# MB.net
KiCad netlist of a schematic drawn in EAGLE
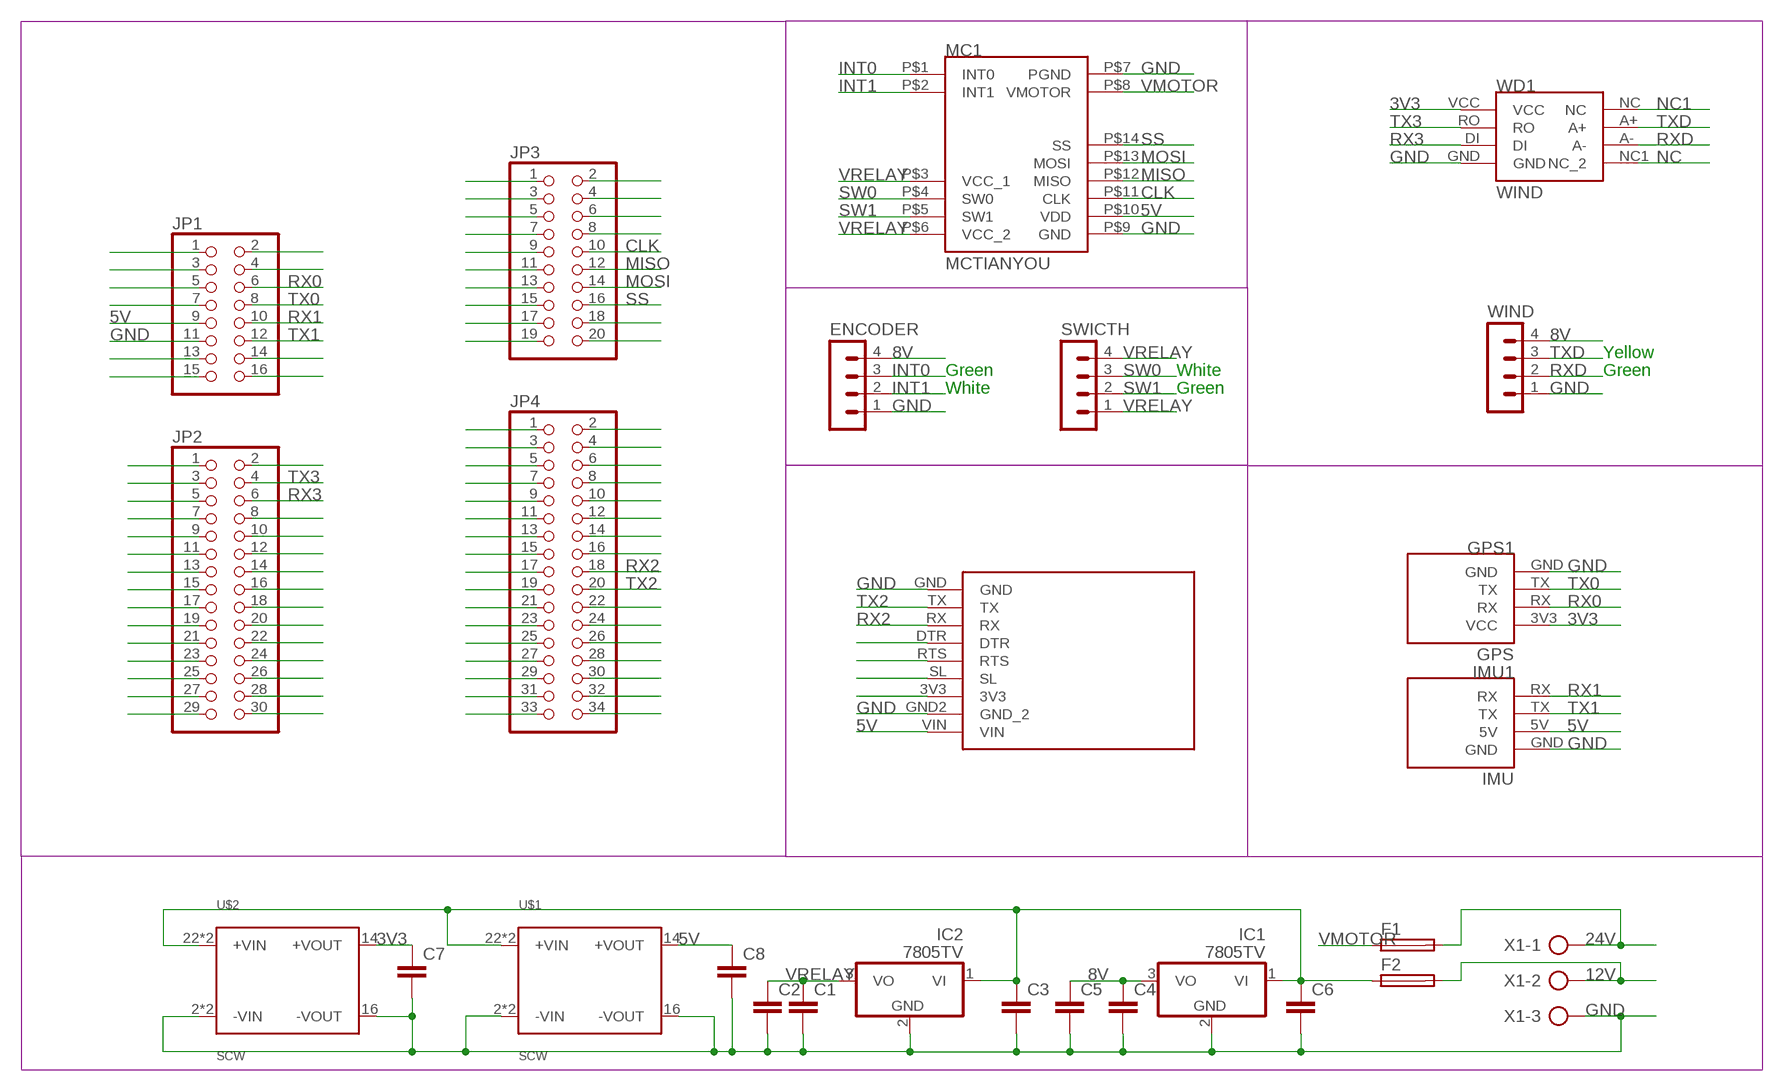
[diagram p0: schematic, sheet 1]

(export (version "E")
  (design (tool "Eeschema 10.0.6"))
  (components
    (comp (ref "C1")
      (value "C-EUC0603")
      (footprint "eagle-import:C0603")
      (libsource (lib "eagle-import") (part "C-EUC0603"))
    )
    (comp (ref "C2")
      (value "C-EUC0603")
      (footprint "eagle-import:C0603")
      (libsource (lib "eagle-import") (part "C-EUC0603"))
    )
    (comp (ref "C3")
      (value "C-EUC0603")
      (footprint "eagle-import:C0603")
      (libsource (lib "eagle-import") (part "C-EUC0603"))
    )
    (comp (ref "C4")
      (value "C-EUC0603")
      (footprint "eagle-import:C0603")
      (libsource (lib "eagle-import") (part "C-EUC0603"))
    )
    (comp (ref "C5")
      (value "C-EUC0603")
      (footprint "eagle-import:C0603")
      (libsource (lib "eagle-import") (part "C-EUC0603"))
    )
    (comp (ref "C6")
      (value "C-EUC0603")
      (footprint "eagle-import:C0603")
      (libsource (lib "eagle-import") (part "C-EUC0603"))
    )
    (comp (ref "C7")
      (value "C-EUC0603")
      (footprint "eagle-import:C0603")
      (libsource (lib "eagle-import") (part "C-EUC0603"))
    )
    (comp (ref "C8")
      (value "C-EUC0603")
      (footprint "eagle-import:C0603")
      (libsource (lib "eagle-import") (part "C-EUC0603"))
    )
    (comp (ref "ENCODER")
      (value "MA04-1")
      (footprint "eagle-import:MA04-1")
      (libsource (lib "eagle-import") (part "MA04-1"))
    )
    (comp (ref "F1")
      (value "SH22,5")
      (footprint "eagle-import:SH22,5")
      (fields (field (name "MF") "SCHURTER") (field (name "MPN") "0031.8201"))
      (libsource (lib "eagle-import") (part "SH22,5"))
    )
    (comp (ref "F2")
      (value "SH22,5")
      (footprint "eagle-import:SH22,5")
      (fields (field (name "MF") "SCHURTER") (field (name "MPN") "0031.8201"))
      (libsource (lib "eagle-import") (part "SH22,5"))
    )
    (comp (ref "GPS1")
      (value "GPS")
      (footprint "eagle-import:GPS")
      (libsource (lib "eagle-import") (part "GPS"))
    )
    (comp (ref "IC1")
      (value "7805TV")
      (footprint "eagle-import:TO220V")
      (libsource (lib "eagle-import") (part "78TV05"))
    )
    (comp (ref "IC2")
      (value "7805TV")
      (footprint "eagle-import:TO220V")
      (libsource (lib "eagle-import") (part "78TV05"))
    )
    (comp (ref "IMU1")
      (value "IMU")
      (footprint "eagle-import:IMU")
      (libsource (lib "eagle-import") (part "IMU"))
    )
    (comp (ref "JP1")
      (value "PINHD-2X8")
      (footprint "eagle-import:2X08")
      (libsource (lib "eagle-import") (part "PINHD-2X8"))
    )
    (comp (ref "JP2")
      (value "PINHD-2X15")
      (footprint "eagle-import:2X15")
      (libsource (lib "eagle-import") (part "PINHD-2X15"))
    )
    (comp (ref "JP3")
      (value "PINHD-2X10")
      (footprint "eagle-import:2X10")
      (libsource (lib "eagle-import") (part "PINHD-2X10"))
    )
    (comp (ref "JP4")
      (value "PINHD-2X17")
      (footprint "eagle-import:2X17")
      (libsource (lib "eagle-import") (part "PINHD-2X17"))
    )
    (comp (ref "MC1")
      (value "MCTIANYOU")
      (footprint "eagle-import:MCTIANYOU")
      (libsource (lib "eagle-import") (part "MCTIANYOU"))
    )
    (comp (ref "SWICTH")
      (value "MA04-1")
      (footprint "eagle-import:MA04-1")
      (libsource (lib "eagle-import") (part "MA04-1"))
    )
    (comp (ref "U$1")
      (value "SCW")
      (footprint "eagle-import:SCW")
      (libsource (lib "eagle-import") (part "SCW"))
    )
    (comp (ref "U$2")
      (value "SCW")
      (footprint "eagle-import:SCW")
      (libsource (lib "eagle-import") (part "SCW"))
    )
    (comp (ref "WD1")
      (value "WIND")
      (footprint "eagle-import:WIND")
      (libsource (lib "eagle-import") (part "WIND"))
    )
    (comp (ref "WIND")
      (value "MA04-1")
      (footprint "eagle-import:MA04-1")
      (libsource (lib "eagle-import") (part "MA04-1"))
    )
    (comp (ref "X1")
      (value "AK300/3")
      (footprint "eagle-import:AK300_3")
      (libsource (lib "eagle-import") (part "AK300/3"))
    )
    (comp (ref "XBEE1")
      (value "XBEE")
      (footprint "eagle-import:XBEE")
      (libsource (lib "eagle-import") (part "XBEE"))
    )
  )
  (nets
    (net (code "1") (name "/3V3") (class "Default")
      (node (ref "C7") (pin "1") (pinfunction "1_1") (pintype "passive"))
      (node (ref "GPS1") (pin "3V3") (pinfunction "VCC_3V3") (pintype "bidirectional"))
      (node (ref "U$2") (pin "14") (pinfunction "+VOUT_14") (pintype "output"))
      (node (ref "WD1") (pin "VCC") (pinfunction "VCC_VCC") (pintype "bidirectional"))
    )
    (net (code "2") (name "/5V") (class "Default")
      (node (ref "C8") (pin "1") (pinfunction "1_1") (pintype "passive"))
      (node (ref "IMU1") (pin "5V") (pinfunction "5V_5V") (pintype "bidirectional"))
      (node (ref "JP1") (pin "9") (pinfunction "9_9") (pintype "passive"))
      (node (ref "MC1") (pin "P$10") (pinfunction "VDD_P$10") (pintype "bidirectional"))
      (node (ref "U$1") (pin "14") (pinfunction "+VOUT_14") (pintype "output"))
      (node (ref "XBEE1") (pin "VIN") (pinfunction "VIN_VIN") (pintype "bidirectional"))
    )
    (net (code "3") (name "/8V") (class "Default")
      (node (ref "C4") (pin "1") (pinfunction "1_1") (pintype "passive"))
      (node (ref "C5") (pin "1") (pinfunction "1_1") (pintype "passive"))
      (node (ref "ENCODER") (pin "4") (pinfunction "4_4") (pintype "passive"))
      (node (ref "IC1") (pin "3") (pinfunction "VO_3") (pintype "passive"))
      (node (ref "WIND") (pin "4") (pinfunction "4_4") (pintype "passive"))
    )
    (net (code "4") (name "/12V") (class "Default")
      (node (ref "F2") (pin "2") (pinfunction "2_2") (pintype "passive"))
      (node (ref "X1") (pin "2") (pinfunction "KL_2") (pintype "passive"))
    )
    (net (code "5") (name "/24V") (class "Default")
      (node (ref "F1") (pin "2") (pinfunction "2_2") (pintype "passive"))
      (node (ref "X1") (pin "1") (pinfunction "KL_1") (pintype "passive"))
    )
    (net (code "6") (name "/CLK") (class "Default")
      (node (ref "JP3") (pin "10") (pinfunction "10_10") (pintype "passive"))
      (node (ref "MC1") (pin "P$11") (pinfunction "CLK_P$11") (pintype "bidirectional"))
    )
    (net (code "7") (name "/GND") (class "Default")
      (node (ref "C1") (pin "2") (pinfunction "2_2") (pintype "passive"))
      (node (ref "C2") (pin "2") (pinfunction "2_2") (pintype "passive"))
      (node (ref "C3") (pin "2") (pinfunction "2_2") (pintype "passive"))
      (node (ref "C4") (pin "2") (pinfunction "2_2") (pintype "passive"))
      (node (ref "C5") (pin "2") (pinfunction "2_2") (pintype "passive"))
      (node (ref "C6") (pin "2") (pinfunction "2_2") (pintype "passive"))
      (node (ref "C7") (pin "2") (pinfunction "2_2") (pintype "passive"))
      (node (ref "C8") (pin "2") (pinfunction "2_2") (pintype "passive"))
      (node (ref "ENCODER") (pin "1") (pinfunction "1_1") (pintype "passive"))
      (node (ref "GPS1") (pin "GND") (pinfunction "GND_GND") (pintype "bidirectional"))
      (node (ref "IC1") (pin "2") (pinfunction "GND_2") (pintype "passive"))
      (node (ref "IC2") (pin "2") (pinfunction "GND_2") (pintype "passive"))
      (node (ref "IMU1") (pin "GND") (pinfunction "GND_GND") (pintype "bidirectional"))
      (node (ref "JP1") (pin "11") (pinfunction "11_11") (pintype "passive"))
      (node (ref "MC1") (pin "P$7") (pinfunction "PGND_P$7") (pintype "bidirectional"))
      (node (ref "MC1") (pin "P$9") (pinfunction "GND_P$9") (pintype "bidirectional"))
      (node (ref "U$1") (pin "16") (pinfunction "-VOUT_16") (pintype "output"))
      (node (ref "U$1") (pin "2") (pinfunction "-VIN_2") (pintype "input"))
      (node (ref "U$1") (pin "3") (pinfunction "-VIN_3") (pintype "input"))
      (node (ref "U$2") (pin "16") (pinfunction "-VOUT_16") (pintype "output"))
      (node (ref "U$2") (pin "2") (pinfunction "-VIN_2") (pintype "input"))
      (node (ref "U$2") (pin "3") (pinfunction "-VIN_3") (pintype "input"))
      (node (ref "WD1") (pin "GND") (pinfunction "GND_GND") (pintype "bidirectional"))
      (node (ref "WIND") (pin "1") (pinfunction "1_1") (pintype "passive"))
      (node (ref "X1") (pin "3") (pinfunction "KL_3") (pintype "passive"))
      (node (ref "XBEE1") (pin "GND") (pinfunction "GND_GND") (pintype "bidirectional"))
      (node (ref "XBEE1") (pin "GND2") (pinfunction "GND_2_GND2") (pintype "bidirectional"))
    )
    (net (code "8") (name "/INT0") (class "Default")
      (node (ref "ENCODER") (pin "3") (pinfunction "3_3") (pintype "passive"))
      (node (ref "MC1") (pin "P$1") (pinfunction "INT0_P$1") (pintype "bidirectional"))
    )
    (net (code "9") (name "/INT1") (class "Default")
      (node (ref "ENCODER") (pin "2") (pinfunction "2_2") (pintype "passive"))
      (node (ref "MC1") (pin "P$2") (pinfunction "INT1_P$2") (pintype "bidirectional"))
    )
    (net (code "10") (name "/MISO") (class "Default")
      (node (ref "JP3") (pin "12") (pinfunction "12_12") (pintype "passive"))
      (node (ref "MC1") (pin "P$12") (pinfunction "MISO_P$12") (pintype "bidirectional"))
    )
    (net (code "11") (name "/MOSI") (class "Default")
      (node (ref "JP3") (pin "14") (pinfunction "14_14") (pintype "passive"))
      (node (ref "MC1") (pin "P$13") (pinfunction "MOSI_P$13") (pintype "bidirectional"))
    )
    (net (code "12") (name "/NC") (class "Default")
      (node (ref "WD1") (pin "NC1") (pinfunction "NC_2_NC1") (pintype "bidirectional"))
    )
    (net (code "13") (name "/NC1") (class "Default")
      (node (ref "WD1") (pin "NC") (pinfunction "NC_NC") (pintype "bidirectional"))
    )
    (net (code "14") (name "/RX0") (class "Default")
      (node (ref "GPS1") (pin "RX") (pinfunction "RX_RX") (pintype "bidirectional"))
      (node (ref "JP1") (pin "6") (pinfunction "6_6") (pintype "passive"))
    )
    (net (code "15") (name "/RX1") (class "Default")
      (node (ref "IMU1") (pin "RX") (pinfunction "RX_RX") (pintype "bidirectional"))
      (node (ref "JP1") (pin "10") (pinfunction "10_10") (pintype "passive"))
    )
    (net (code "16") (name "/RX2") (class "Default")
      (node (ref "JP4") (pin "18") (pinfunction "18_18") (pintype "passive"))
      (node (ref "XBEE1") (pin "RX") (pinfunction "RX_RX") (pintype "bidirectional"))
    )
    (net (code "17") (name "/RX3") (class "Default")
      (node (ref "JP2") (pin "6") (pinfunction "6_6") (pintype "passive"))
      (node (ref "WD1") (pin "DI") (pinfunction "DI_DI") (pintype "bidirectional"))
    )
    (net (code "18") (name "/RXD") (class "Default")
      (node (ref "WD1") (pin "A-") (pinfunction "A-_A-") (pintype "bidirectional"))
      (node (ref "WIND") (pin "2") (pinfunction "2_2") (pintype "passive"))
    )
    (net (code "19") (name "/SS") (class "Default")
      (node (ref "JP3") (pin "16") (pinfunction "16_16") (pintype "passive"))
      (node (ref "MC1") (pin "P$14") (pinfunction "SS_P$14") (pintype "bidirectional"))
    )
    (net (code "20") (name "/SW0") (class "Default")
      (node (ref "MC1") (pin "P$4") (pinfunction "SW0_P$4") (pintype "bidirectional"))
      (node (ref "SWICTH") (pin "3") (pinfunction "3_3") (pintype "passive"))
    )
    (net (code "21") (name "/SW1") (class "Default")
      (node (ref "MC1") (pin "P$5") (pinfunction "SW1_P$5") (pintype "bidirectional"))
      (node (ref "SWICTH") (pin "2") (pinfunction "2_2") (pintype "passive"))
    )
    (net (code "22") (name "/TX0") (class "Default")
      (node (ref "GPS1") (pin "TX") (pinfunction "TX_TX") (pintype "bidirectional"))
      (node (ref "JP1") (pin "8") (pinfunction "8_8") (pintype "passive"))
    )
    (net (code "23") (name "/TX1") (class "Default")
      (node (ref "IMU1") (pin "TX") (pinfunction "TX_TX") (pintype "bidirectional"))
      (node (ref "JP1") (pin "12") (pinfunction "12_12") (pintype "passive"))
    )
    (net (code "24") (name "/TX2") (class "Default")
      (node (ref "JP4") (pin "20") (pinfunction "20_20") (pintype "passive"))
      (node (ref "XBEE1") (pin "TX") (pinfunction "TX_TX") (pintype "bidirectional"))
    )
    (net (code "25") (name "/TX3") (class "Default")
      (node (ref "JP2") (pin "4") (pinfunction "4_4") (pintype "passive"))
      (node (ref "WD1") (pin "RO") (pinfunction "RO_RO") (pintype "bidirectional"))
    )
    (net (code "26") (name "/TXD") (class "Default")
      (node (ref "WD1") (pin "A+") (pinfunction "A+_A+") (pintype "bidirectional"))
      (node (ref "WIND") (pin "3") (pinfunction "3_3") (pintype "passive"))
    )
    (net (code "27") (name "/VMOTOR") (class "Default")
      (node (ref "F1") (pin "1") (pinfunction "1_1") (pintype "passive"))
      (node (ref "MC1") (pin "P$8") (pinfunction "VMOTOR_P$8") (pintype "bidirectional"))
    )
    (net (code "28") (name "/VRELAY") (class "Default")
      (node (ref "C1") (pin "1") (pinfunction "1_1") (pintype "passive"))
      (node (ref "C2") (pin "1") (pinfunction "1_1") (pintype "passive"))
      (node (ref "IC2") (pin "3") (pinfunction "VO_3") (pintype "passive"))
      (node (ref "MC1") (pin "P$3") (pinfunction "VCC_1_P$3") (pintype "bidirectional"))
      (node (ref "MC1") (pin "P$6") (pinfunction "VCC_2_P$6") (pintype "bidirectional"))
      (node (ref "SWICTH") (pin "1") (pinfunction "1_1") (pintype "passive"))
      (node (ref "SWICTH") (pin "4") (pinfunction "4_4") (pintype "passive"))
    )
    (net (code "29") (name "Net-(IC1-VI)") (class "Default")
      (node (ref "C3") (pin "1") (pinfunction "1_1") (pintype "passive"))
      (node (ref "C6") (pin "1") (pinfunction "1_1") (pintype "passive"))
      (node (ref "F2") (pin "1") (pinfunction "1_1") (pintype "passive"))
      (node (ref "IC1") (pin "1") (pinfunction "VI_1") (pintype "input"))
      (node (ref "IC2") (pin "1") (pinfunction "VI_1") (pintype "input"))
      (node (ref "U$1") (pin "22") (pinfunction "+VIN_22") (pintype "input"))
      (node (ref "U$1") (pin "23") (pinfunction "+VIN_23") (pintype "input"))
      (node (ref "U$2") (pin "22") (pinfunction "+VIN_22") (pintype "input"))
      (node (ref "U$2") (pin "23") (pinfunction "+VIN_23") (pintype "input"))
    )
    (net (code "30") (name "unconnected-(JP1-Pad1)") (class "Default")
      (node (ref "JP1") (pin "1") (pinfunction "1_1") (pintype "passive"))
    )
    (net (code "31") (name "unconnected-(JP1-Pad2)") (class "Default")
      (node (ref "JP1") (pin "2") (pinfunction "2_2") (pintype "passive"))
    )
    (net (code "32") (name "unconnected-(JP1-Pad3)") (class "Default")
      (node (ref "JP1") (pin "3") (pinfunction "3_3") (pintype "passive"))
    )
    (net (code "33") (name "unconnected-(JP1-Pad4)") (class "Default")
      (node (ref "JP1") (pin "4") (pinfunction "4_4") (pintype "passive"))
    )
    (net (code "34") (name "unconnected-(JP1-Pad5)") (class "Default")
      (node (ref "JP1") (pin "5") (pinfunction "5_5") (pintype "passive"))
    )
    (net (code "35") (name "unconnected-(JP1-Pad7)") (class "Default")
      (node (ref "JP1") (pin "7") (pinfunction "7_7") (pintype "passive"))
    )
    (net (code "36") (name "unconnected-(JP1-Pad13)") (class "Default")
      (node (ref "JP1") (pin "13") (pinfunction "13_13") (pintype "passive"))
    )
    (net (code "37") (name "unconnected-(JP1-Pad14)") (class "Default")
      (node (ref "JP1") (pin "14") (pinfunction "14_14") (pintype "passive"))
    )
    (net (code "38") (name "unconnected-(JP1-Pad15)") (class "Default")
      (node (ref "JP1") (pin "15") (pinfunction "15_15") (pintype "passive"))
    )
    (net (code "39") (name "unconnected-(JP1-Pad16)") (class "Default")
      (node (ref "JP1") (pin "16") (pinfunction "16_16") (pintype "passive"))
    )
    (net (code "40") (name "unconnected-(JP2-Pad1)") (class "Default")
      (node (ref "JP2") (pin "1") (pinfunction "1_1") (pintype "passive"))
    )
    (net (code "41") (name "unconnected-(JP2-Pad2)") (class "Default")
      (node (ref "JP2") (pin "2") (pinfunction "2_2") (pintype "passive"))
    )
    (net (code "42") (name "unconnected-(JP2-Pad3)") (class "Default")
      (node (ref "JP2") (pin "3") (pinfunction "3_3") (pintype "passive"))
    )
    (net (code "43") (name "unconnected-(JP2-Pad5)") (class "Default")
      (node (ref "JP2") (pin "5") (pinfunction "5_5") (pintype "passive"))
    )
    (net (code "44") (name "unconnected-(JP2-Pad7)") (class "Default")
      (node (ref "JP2") (pin "7") (pinfunction "7_7") (pintype "passive"))
    )
    (net (code "45") (name "unconnected-(JP2-Pad8)") (class "Default")
      (node (ref "JP2") (pin "8") (pinfunction "8_8") (pintype "passive"))
    )
    (net (code "46") (name "unconnected-(JP2-Pad9)") (class "Default")
      (node (ref "JP2") (pin "9") (pinfunction "9_9") (pintype "passive"))
    )
    (net (code "47") (name "unconnected-(JP2-Pad10)") (class "Default")
      (node (ref "JP2") (pin "10") (pinfunction "10_10") (pintype "passive"))
    )
    (net (code "48") (name "unconnected-(JP2-Pad11)") (class "Default")
      (node (ref "JP2") (pin "11") (pinfunction "11_11") (pintype "passive"))
    )
    (net (code "49") (name "unconnected-(JP2-Pad12)") (class "Default")
      (node (ref "JP2") (pin "12") (pinfunction "12_12") (pintype "passive"))
    )
    (net (code "50") (name "unconnected-(JP2-Pad13)") (class "Default")
      (node (ref "JP2") (pin "13") (pinfunction "13_13") (pintype "passive"))
    )
    (net (code "51") (name "unconnected-(JP2-Pad14)") (class "Default")
      (node (ref "JP2") (pin "14") (pinfunction "14_14") (pintype "passive"))
    )
    (net (code "52") (name "unconnected-(JP2-Pad15)") (class "Default")
      (node (ref "JP2") (pin "15") (pinfunction "15_15") (pintype "passive"))
    )
    (net (code "53") (name "unconnected-(JP2-Pad16)") (class "Default")
      (node (ref "JP2") (pin "16") (pinfunction "16_16") (pintype "passive"))
    )
    (net (code "54") (name "unconnected-(JP2-Pad17)") (class "Default")
      (node (ref "JP2") (pin "17") (pinfunction "17_17") (pintype "passive"))
    )
    (net (code "55") (name "unconnected-(JP2-Pad18)") (class "Default")
      (node (ref "JP2") (pin "18") (pinfunction "18_18") (pintype "passive"))
    )
    (net (code "56") (name "unconnected-(JP2-Pad19)") (class "Default")
      (node (ref "JP2") (pin "19") (pinfunction "19_19") (pintype "passive"))
    )
    (net (code "57") (name "unconnected-(JP2-Pad20)") (class "Default")
      (node (ref "JP2") (pin "20") (pinfunction "20_20") (pintype "passive"))
    )
    (net (code "58") (name "unconnected-(JP2-Pad21)") (class "Default")
      (node (ref "JP2") (pin "21") (pinfunction "21_21") (pintype "passive"))
    )
    (net (code "59") (name "unconnected-(JP2-Pad22)") (class "Default")
      (node (ref "JP2") (pin "22") (pinfunction "22_22") (pintype "passive"))
    )
    (net (code "60") (name "unconnected-(JP2-Pad23)") (class "Default")
      (node (ref "JP2") (pin "23") (pinfunction "23_23") (pintype "passive"))
    )
    (net (code "61") (name "unconnected-(JP2-Pad24)") (class "Default")
      (node (ref "JP2") (pin "24") (pinfunction "24_24") (pintype "passive"))
    )
    (net (code "62") (name "unconnected-(JP2-Pad25)") (class "Default")
      (node (ref "JP2") (pin "25") (pinfunction "25_25") (pintype "passive"))
    )
    (net (code "63") (name "unconnected-(JP2-Pad26)") (class "Default")
      (node (ref "JP2") (pin "26") (pinfunction "26_26") (pintype "passive"))
    )
    (net (code "64") (name "unconnected-(JP2-Pad27)") (class "Default")
      (node (ref "JP2") (pin "27") (pinfunction "27_27") (pintype "passive"))
    )
    (net (code "65") (name "unconnected-(JP2-Pad28)") (class "Default")
      (node (ref "JP2") (pin "28") (pinfunction "28_28") (pintype "passive"))
    )
    (net (code "66") (name "unconnected-(JP2-Pad29)") (class "Default")
      (node (ref "JP2") (pin "29") (pinfunction "29_29") (pintype "passive"))
    )
    (net (code "67") (name "unconnected-(JP2-Pad30)") (class "Default")
      (node (ref "JP2") (pin "30") (pinfunction "30_30") (pintype "passive"))
    )
    (net (code "68") (name "unconnected-(JP3-Pad1)") (class "Default")
      (node (ref "JP3") (pin "1") (pinfunction "1_1") (pintype "passive"))
    )
    (net (code "69") (name "unconnected-(JP3-Pad2)") (class "Default")
      (node (ref "JP3") (pin "2") (pinfunction "2_2") (pintype "passive"))
    )
    (net (code "70") (name "unconnected-(JP3-Pad3)") (class "Default")
      (node (ref "JP3") (pin "3") (pinfunction "3_3") (pintype "passive"))
    )
    (net (code "71") (name "unconnected-(JP3-Pad4)") (class "Default")
      (node (ref "JP3") (pin "4") (pinfunction "4_4") (pintype "passive"))
    )
    (net (code "72") (name "unconnected-(JP3-Pad5)") (class "Default")
      (node (ref "JP3") (pin "5") (pinfunction "5_5") (pintype "passive"))
    )
    (net (code "73") (name "unconnected-(JP3-Pad6)") (class "Default")
      (node (ref "JP3") (pin "6") (pinfunction "6_6") (pintype "passive"))
    )
    (net (code "74") (name "unconnected-(JP3-Pad7)") (class "Default")
      (node (ref "JP3") (pin "7") (pinfunction "7_7") (pintype "passive"))
    )
    (net (code "75") (name "unconnected-(JP3-Pad8)") (class "Default")
      (node (ref "JP3") (pin "8") (pinfunction "8_8") (pintype "passive"))
    )
    (net (code "76") (name "unconnected-(JP3-Pad9)") (class "Default")
      (node (ref "JP3") (pin "9") (pinfunction "9_9") (pintype "passive"))
    )
    (net (code "77") (name "unconnected-(JP3-Pad11)") (class "Default")
      (node (ref "JP3") (pin "11") (pinfunction "11_11") (pintype "passive"))
    )
    (net (code "78") (name "unconnected-(JP3-Pad13)") (class "Default")
      (node (ref "JP3") (pin "13") (pinfunction "13_13") (pintype "passive"))
    )
    (net (code "79") (name "unconnected-(JP3-Pad15)") (class "Default")
      (node (ref "JP3") (pin "15") (pinfunction "15_15") (pintype "passive"))
    )
    (net (code "80") (name "unconnected-(JP3-Pad17)") (class "Default")
      (node (ref "JP3") (pin "17") (pinfunction "17_17") (pintype "passive"))
    )
    (net (code "81") (name "unconnected-(JP3-Pad18)") (class "Default")
      (node (ref "JP3") (pin "18") (pinfunction "18_18") (pintype "passive"))
    )
    (net (code "82") (name "unconnected-(JP3-Pad19)") (class "Default")
      (node (ref "JP3") (pin "19") (pinfunction "19_19") (pintype "passive"))
    )
    (net (code "83") (name "unconnected-(JP3-Pad20)") (class "Default")
      (node (ref "JP3") (pin "20") (pinfunction "20_20") (pintype "passive"))
    )
    (net (code "84") (name "unconnected-(JP4-Pad1)") (class "Default")
      (node (ref "JP4") (pin "1") (pinfunction "1_1") (pintype "passive"))
    )
    (net (code "85") (name "unconnected-(JP4-Pad2)") (class "Default")
      (node (ref "JP4") (pin "2") (pinfunction "2_2") (pintype "passive"))
    )
    (net (code "86") (name "unconnected-(JP4-Pad3)") (class "Default")
      (node (ref "JP4") (pin "3") (pinfunction "3_3") (pintype "passive"))
    )
    (net (code "87") (name "unconnected-(JP4-Pad4)") (class "Default")
      (node (ref "JP4") (pin "4") (pinfunction "4_4") (pintype "passive"))
    )
    (net (code "88") (name "unconnected-(JP4-Pad5)") (class "Default")
      (node (ref "JP4") (pin "5") (pinfunction "5_5") (pintype "passive"))
    )
    (net (code "89") (name "unconnected-(JP4-Pad6)") (class "Default")
      (node (ref "JP4") (pin "6") (pinfunction "6_6") (pintype "passive"))
    )
    (net (code "90") (name "unconnected-(JP4-Pad7)") (class "Default")
      (node (ref "JP4") (pin "7") (pinfunction "7_7") (pintype "passive"))
    )
    (net (code "91") (name "unconnected-(JP4-Pad8)") (class "Default")
      (node (ref "JP4") (pin "8") (pinfunction "8_8") (pintype "passive"))
    )
    (net (code "92") (name "unconnected-(JP4-Pad9)") (class "Default")
      (node (ref "JP4") (pin "9") (pinfunction "9_9") (pintype "passive"))
    )
    (net (code "93") (name "unconnected-(JP4-Pad10)") (class "Default")
      (node (ref "JP4") (pin "10") (pinfunction "10_10") (pintype "passive"))
    )
    (net (code "94") (name "unconnected-(JP4-Pad11)") (class "Default")
      (node (ref "JP4") (pin "11") (pinfunction "11_11") (pintype "passive"))
    )
    (net (code "95") (name "unconnected-(JP4-Pad12)") (class "Default")
      (node (ref "JP4") (pin "12") (pinfunction "12_12") (pintype "passive"))
    )
    (net (code "96") (name "unconnected-(JP4-Pad13)") (class "Default")
      (node (ref "JP4") (pin "13") (pinfunction "13_13") (pintype "passive"))
    )
    (net (code "97") (name "unconnected-(JP4-Pad14)") (class "Default")
      (node (ref "JP4") (pin "14") (pinfunction "14_14") (pintype "passive"))
    )
    (net (code "98") (name "unconnected-(JP4-Pad15)") (class "Default")
      (node (ref "JP4") (pin "15") (pinfunction "15_15") (pintype "passive"))
    )
    (net (code "99") (name "unconnected-(JP4-Pad16)") (class "Default")
      (node (ref "JP4") (pin "16") (pinfunction "16_16") (pintype "passive"))
    )
    (net (code "100") (name "unconnected-(JP4-Pad17)") (class "Default")
      (node (ref "JP4") (pin "17") (pinfunction "17_17") (pintype "passive"))
    )
    (net (code "101") (name "unconnected-(JP4-Pad19)") (class "Default")
      (node (ref "JP4") (pin "19") (pinfunction "19_19") (pintype "passive"))
    )
    (net (code "102") (name "unconnected-(JP4-Pad21)") (class "Default")
      (node (ref "JP4") (pin "21") (pinfunction "21_21") (pintype "passive"))
    )
    (net (code "103") (name "unconnected-(JP4-Pad22)") (class "Default")
      (node (ref "JP4") (pin "22") (pinfunction "22_22") (pintype "passive"))
    )
    (net (code "104") (name "unconnected-(JP4-Pad23)") (class "Default")
      (node (ref "JP4") (pin "23") (pinfunction "23_23") (pintype "passive"))
    )
    (net (code "105") (name "unconnected-(JP4-Pad24)") (class "Default")
      (node (ref "JP4") (pin "24") (pinfunction "24_24") (pintype "passive"))
    )
    (net (code "106") (name "unconnected-(JP4-Pad25)") (class "Default")
      (node (ref "JP4") (pin "25") (pinfunction "25_25") (pintype "passive"))
    )
    (net (code "107") (name "unconnected-(JP4-Pad26)") (class "Default")
      (node (ref "JP4") (pin "26") (pinfunction "26_26") (pintype "passive"))
    )
    (net (code "108") (name "unconnected-(JP4-Pad27)") (class "Default")
      (node (ref "JP4") (pin "27") (pinfunction "27_27") (pintype "passive"))
    )
    (net (code "109") (name "unconnected-(JP4-Pad28)") (class "Default")
      (node (ref "JP4") (pin "28") (pinfunction "28_28") (pintype "passive"))
    )
    (net (code "110") (name "unconnected-(JP4-Pad29)") (class "Default")
      (node (ref "JP4") (pin "29") (pinfunction "29_29") (pintype "passive"))
    )
    (net (code "111") (name "unconnected-(JP4-Pad30)") (class "Default")
      (node (ref "JP4") (pin "30") (pinfunction "30_30") (pintype "passive"))
    )
    (net (code "112") (name "unconnected-(JP4-Pad31)") (class "Default")
      (node (ref "JP4") (pin "31") (pinfunction "31_31") (pintype "passive"))
    )
    (net (code "113") (name "unconnected-(JP4-Pad32)") (class "Default")
      (node (ref "JP4") (pin "32") (pinfunction "32_32") (pintype "passive"))
    )
    (net (code "114") (name "unconnected-(JP4-Pad33)") (class "Default")
      (node (ref "JP4") (pin "33") (pinfunction "33_33") (pintype "passive"))
    )
    (net (code "115") (name "unconnected-(JP4-Pad34)") (class "Default")
      (node (ref "JP4") (pin "34") (pinfunction "34_34") (pintype "passive"))
    )
    (net (code "116") (name "unconnected-(XBEE1-Pad3V3)") (class "Default")
      (node (ref "XBEE1") (pin "3V3") (pinfunction "3V3_3V3") (pintype "bidirectional"))
    )
    (net (code "117") (name "unconnected-(XBEE1-PadDTR)") (class "Default")
      (node (ref "XBEE1") (pin "DTR") (pinfunction "DTR_DTR") (pintype "bidirectional"))
    )
    (net (code "118") (name "unconnected-(XBEE1-PadRTS)") (class "Default")
      (node (ref "XBEE1") (pin "RTS") (pinfunction "RTS_RTS") (pintype "bidirectional"))
    )
    (net (code "119") (name "unconnected-(XBEE1-PadSL)") (class "Default")
      (node (ref "XBEE1") (pin "SL") (pinfunction "SL_SL") (pintype "bidirectional"))
    )
  )
)
